# PIR_Sensor_driver_v2.net
KiCad netlist of a schematic drawn in Altium Designer
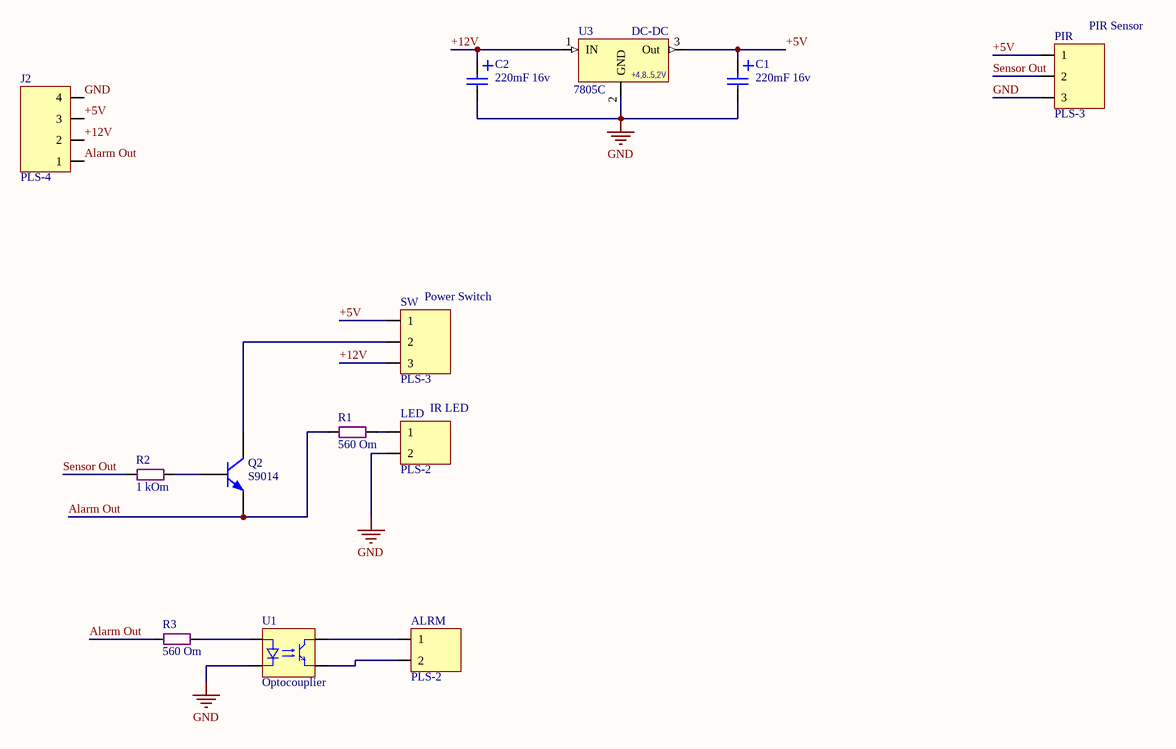
[diagram p0: PIR Sensor driver v2.SchDoc]

(export (version "E")
  (design (tool "Eeschema 10.0.6"))
  (components
    (comp (ref "ALRM")
      (value "PLS-2")
      (footprint "Connector:Line 2.54 x 2")
      (description "Vert, Sgl line, Male")
      (libsource (lib "Connector") (part "PLS-2"))
    )
    (comp (ref "C1")
      (value "220mF 16v")
      (footprint "Capacitor:Cap E p4mm D6.5xH11")
      (description "Capacitor")
      (libsource (lib "Capacitor") (part "Cap E 220mF x 16V"))
    )
    (comp (ref "C2")
      (value "220mF 16v")
      (footprint "Capacitor:Cap E p2mm D6.5xH11")
      (description "Capacitor")
      (libsource (lib "Capacitor") (part "Cap E 220mF x 16V"))
    )
    (comp (ref "J2")
      (value "PLS-4")
      (footprint "Connector:Line 2.54 X 4")
      (description "Vert, Sgl line, Male")
      (libsource (lib "Connector") (part "PLS-4"))
    )
    (comp (ref "LED")
      (value "PLS-2")
      (footprint "Connector:Line 2.54 x 2")
      (description "Vert, Sgl line, Male")
      (libsource (lib "Connector") (part "PLS-2"))
    )
    (comp (ref "PIR")
      (value "PLS-3")
      (footprint "Connector:Line 2.54 X 3")
      (description "Vert, Sgl line, Male")
      (libsource (lib "Connector") (part "PLS-3"))
    )
    (comp (ref "Q2")
      (value "S9014")
      (footprint "GeneralCases:TO-92 2.54 (EBC)")
      (description "NPN Bipolar Transistor")
      (fields (field (name "PUBLISHER") "Altium Limited"))
      (libsource (lib "Transistor") (part "S9014"))
    )
    (comp (ref "R1")
      (value "560 Om")
      (footprint "SMD 0805 (2012)")
      (libsource (lib "PassiveComponents") (part "Res SMD 0805"))
    )
    (comp (ref "R2")
      (value "1 kOm")
      (footprint "SMD 0805 (2012)")
      (libsource (lib "PassiveComponents") (part "Res SMD 0805"))
    )
    (comp (ref "R3")
      (value "560 Om")
      (footprint "SMD 0805 (2012)")
      (libsource (lib "PassiveComponents") (part "Res SMD 0805"))
    )
    (comp (ref "SW")
      (value "PLS-3")
      (footprint "Connector:Line 2.54 X 3")
      (description "Vert, Sgl line, Male")
      (libsource (lib "Connector") (part "PLS-3"))
    )
    (comp (ref "U1")
      (value "Optocouplier")
      (footprint "GeneralCases:DIP-4")
      (libsource (lib "Transistor") (part "Optocouplier LTV 817B"))
    )
    (comp (ref "U3")
      (value "7805C")
      (footprint "GeneralCases:D-PAK")
      (description "Voltage Regulator")
      (fields (field (name "MANUFACTURER") "Интеграл") (field (name "V OUT") "+4,8..5,2V"))
      (libsource (lib "PowerAdjusment") (part "7805C"))
    )
  )
  (nets
    (net (code "1") (name "/+5V") (class "Default")
      (node (ref "C1") (pin "1") (pinfunction "1_1") (pintype "passive"))
      (node (ref "J2") (pin "3") (pinfunction "3_3") (pintype "passive"))
      (node (ref "PIR") (pin "1") (pinfunction "1_1") (pintype "passive"))
      (node (ref "SW") (pin "1") (pinfunction "1_1") (pintype "passive"))
      (node (ref "U3") (pin "3") (pinfunction "Out_3") (pintype "output"))
    )
    (net (code "2") (name "/+12V") (class "Default")
      (node (ref "C2") (pin "1") (pinfunction "1_1") (pintype "passive"))
      (node (ref "J2") (pin "2") (pinfunction "2_2") (pintype "passive"))
      (node (ref "SW") (pin "3") (pinfunction "3_3") (pintype "passive"))
      (node (ref "U3") (pin "1") (pinfunction "IN_1") (pintype "input"))
    )
    (net (code "3") (name "/Alarm Out") (class "Default")
      (node (ref "J2") (pin "1") (pinfunction "1_1") (pintype "passive"))
      (node (ref "Q2") (pin "E") (pinfunction "E_E") (pintype "passive"))
      (node (ref "R1") (pin "1") (pinfunction "1_1") (pintype "passive"))
      (node (ref "R3") (pin "1") (pinfunction "1_1") (pintype "passive"))
    )
    (net (code "4") (name "/Sensor Out") (class "Default")
      (node (ref "PIR") (pin "2") (pinfunction "2_2") (pintype "passive"))
      (node (ref "R2") (pin "1") (pinfunction "1_1") (pintype "passive"))
    )
    (net (code "5") (name "GND") (class "Default")
      (node (ref "C1") (pin "2") (pinfunction "2_2") (pintype "passive"))
      (node (ref "C2") (pin "2") (pinfunction "2_2") (pintype "passive"))
      (node (ref "J2") (pin "4") (pinfunction "4_4") (pintype "passive"))
      (node (ref "LED") (pin "2") (pinfunction "2_2") (pintype "passive"))
      (node (ref "PIR") (pin "3") (pinfunction "3_3") (pintype "passive"))
      (node (ref "U1") (pin "2") (pinfunction "2_2") (pintype "passive"))
      (node (ref "U3") (pin "2") (pinfunction "GND_2") (pintype "passive"))
    )
    (net (code "6") (name "Net-(ALRM-Pad1)") (class "Default")
      (node (ref "ALRM") (pin "1") (pinfunction "1_1") (pintype "passive"))
      (node (ref "U1") (pin "3") (pinfunction "3_3") (pintype "passive"))
    )
    (net (code "7") (name "Net-(ALRM-Pad2)") (class "Default")
      (node (ref "ALRM") (pin "2") (pinfunction "2_2") (pintype "passive"))
      (node (ref "U1") (pin "4") (pinfunction "4_4") (pintype "passive"))
    )
    (net (code "8") (name "Net-(LED-Pad1)") (class "Default")
      (node (ref "LED") (pin "1") (pinfunction "1_1") (pintype "passive"))
      (node (ref "R1") (pin "2") (pinfunction "2_2") (pintype "passive"))
    )
    (net (code "9") (name "Net-(Q2-PadB)") (class "Default")
      (node (ref "Q2") (pin "B") (pinfunction "B_B") (pintype "passive"))
      (node (ref "R2") (pin "2") (pinfunction "2_2") (pintype "passive"))
    )
    (net (code "10") (name "Net-(Q2-PadC)") (class "Default")
      (node (ref "Q2") (pin "C") (pinfunction "C_C") (pintype "passive"))
      (node (ref "SW") (pin "2") (pinfunction "2_2") (pintype "passive"))
    )
    (net (code "11") (name "Net-(R3-Pad2)") (class "Default")
      (node (ref "R3") (pin "2") (pinfunction "2_2") (pintype "passive"))
      (node (ref "U1") (pin "1") (pinfunction "1_1") (pintype "passive"))
    )
  )
)
